# Centerboard_-_Prototype_2_WIP.net
KiCad netlist of a schematic drawn in EAGLE
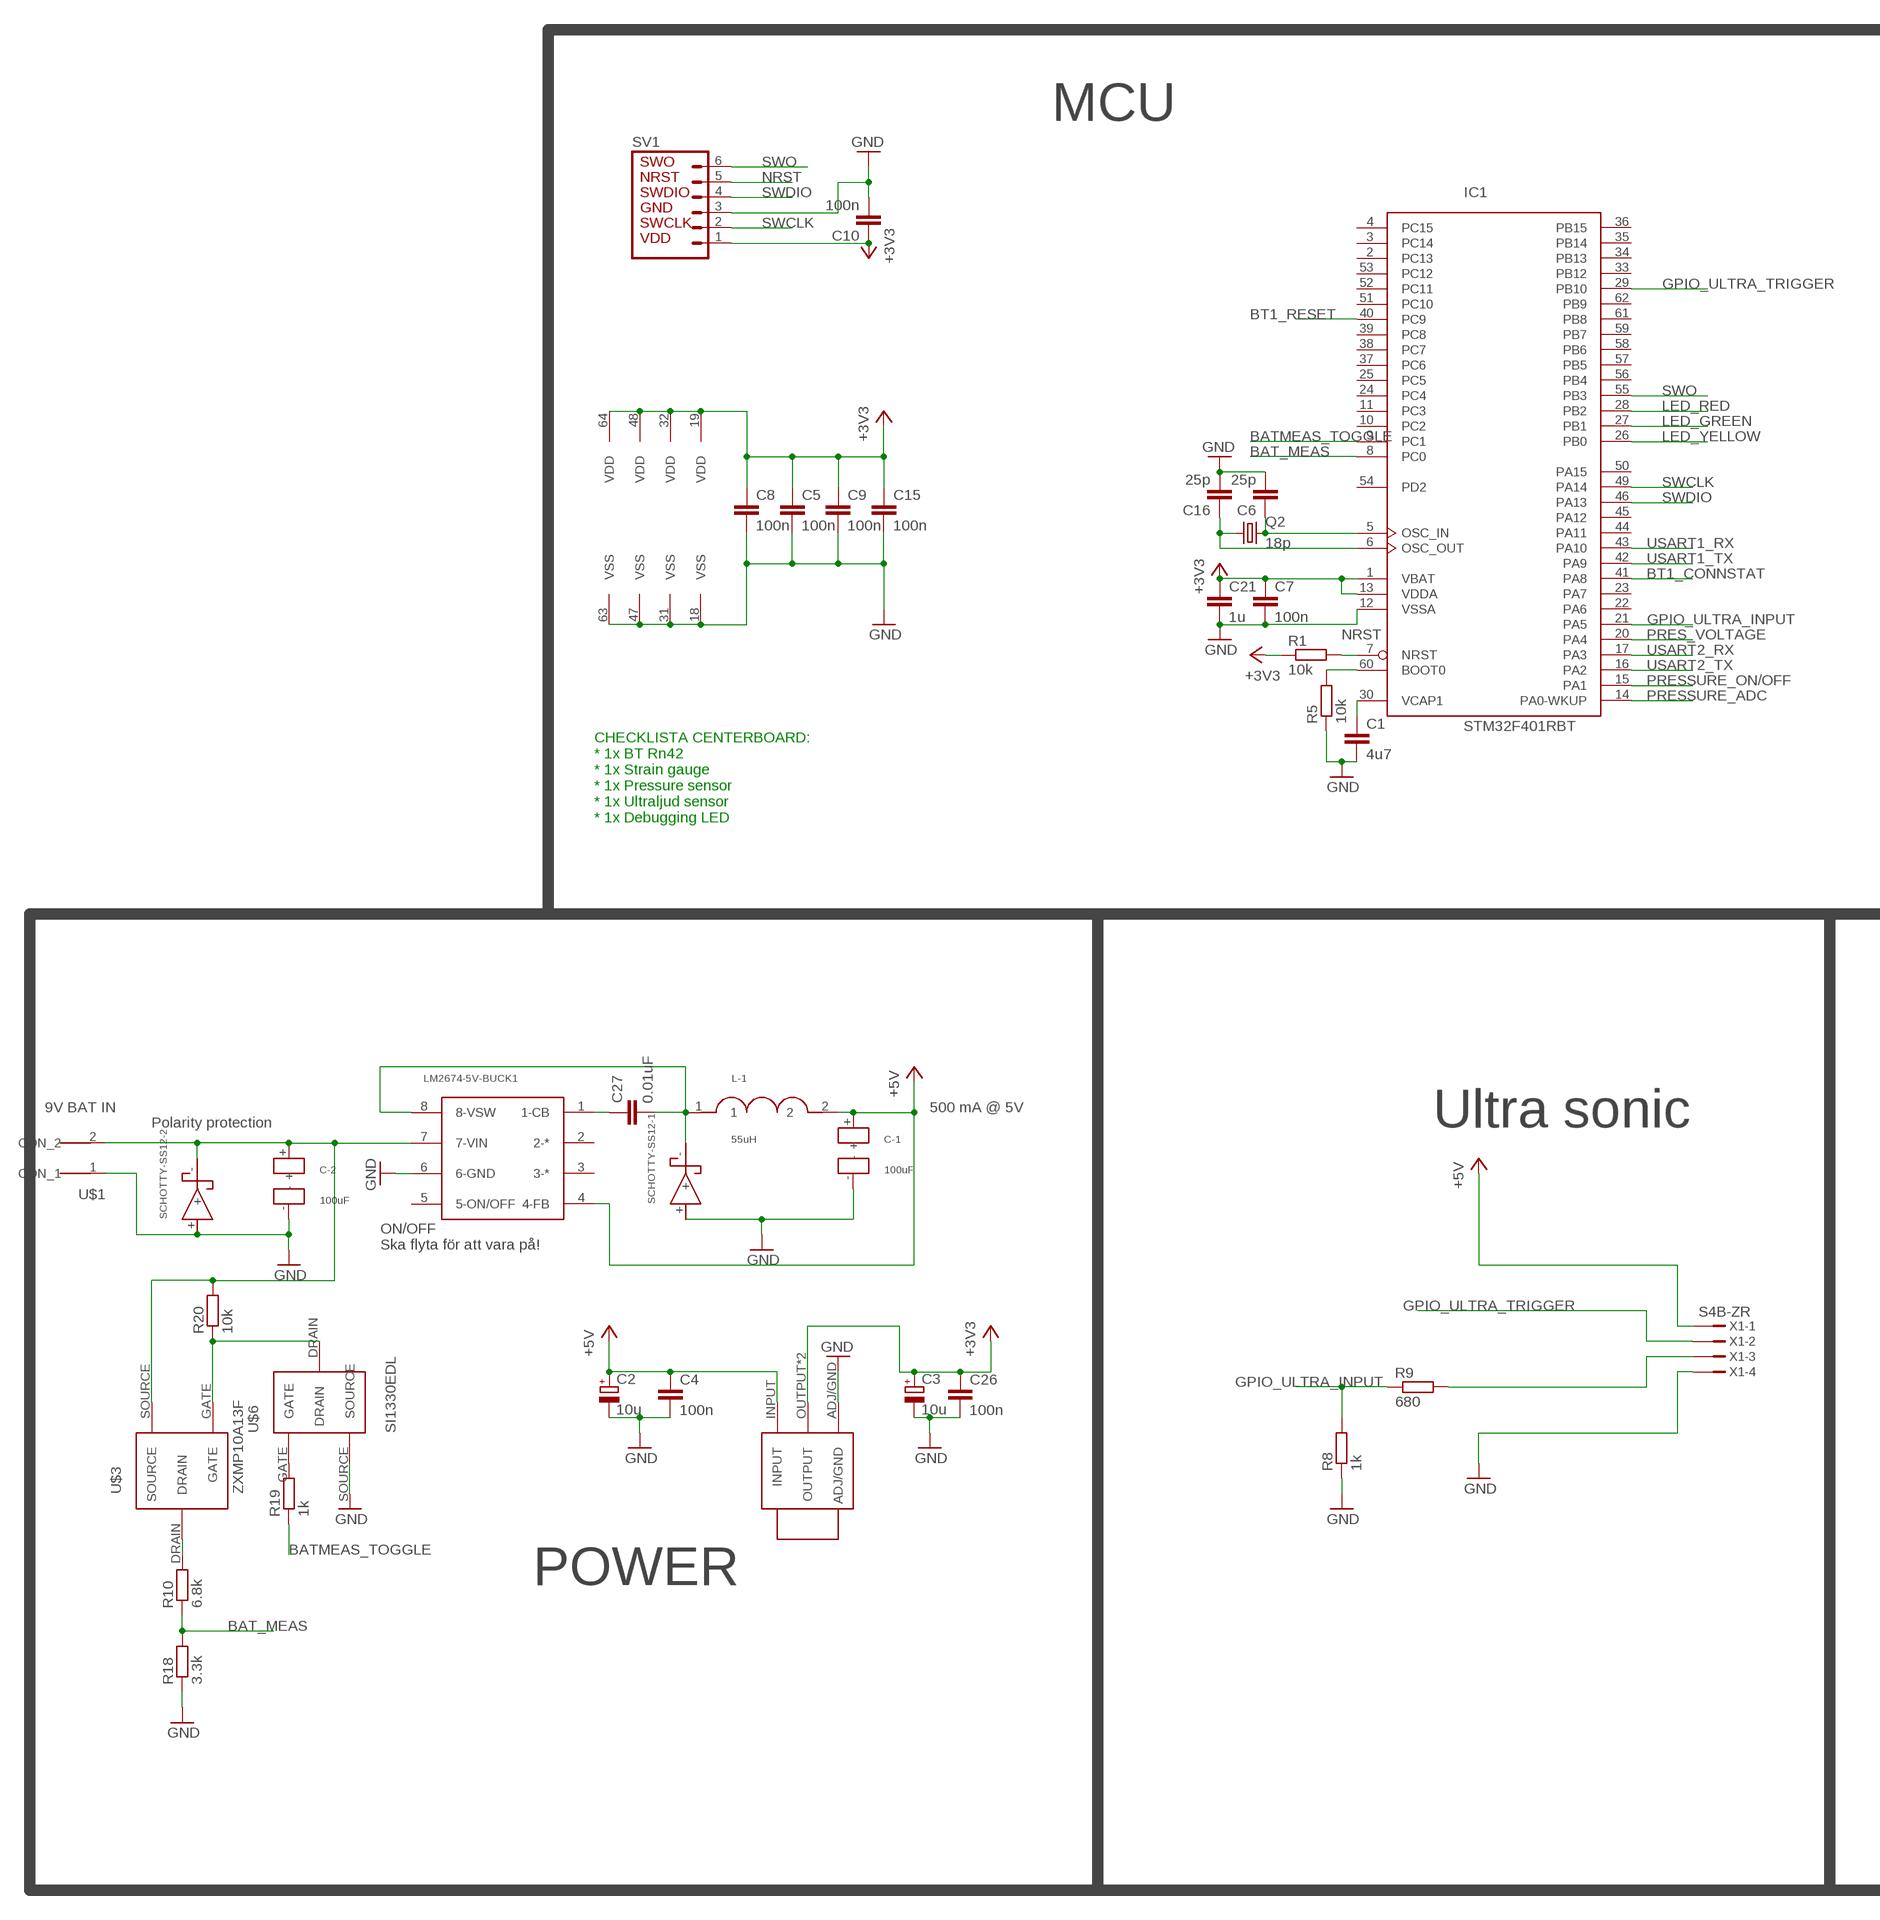
[diagram p0: schematic, sheet 1, part 1 of 2]
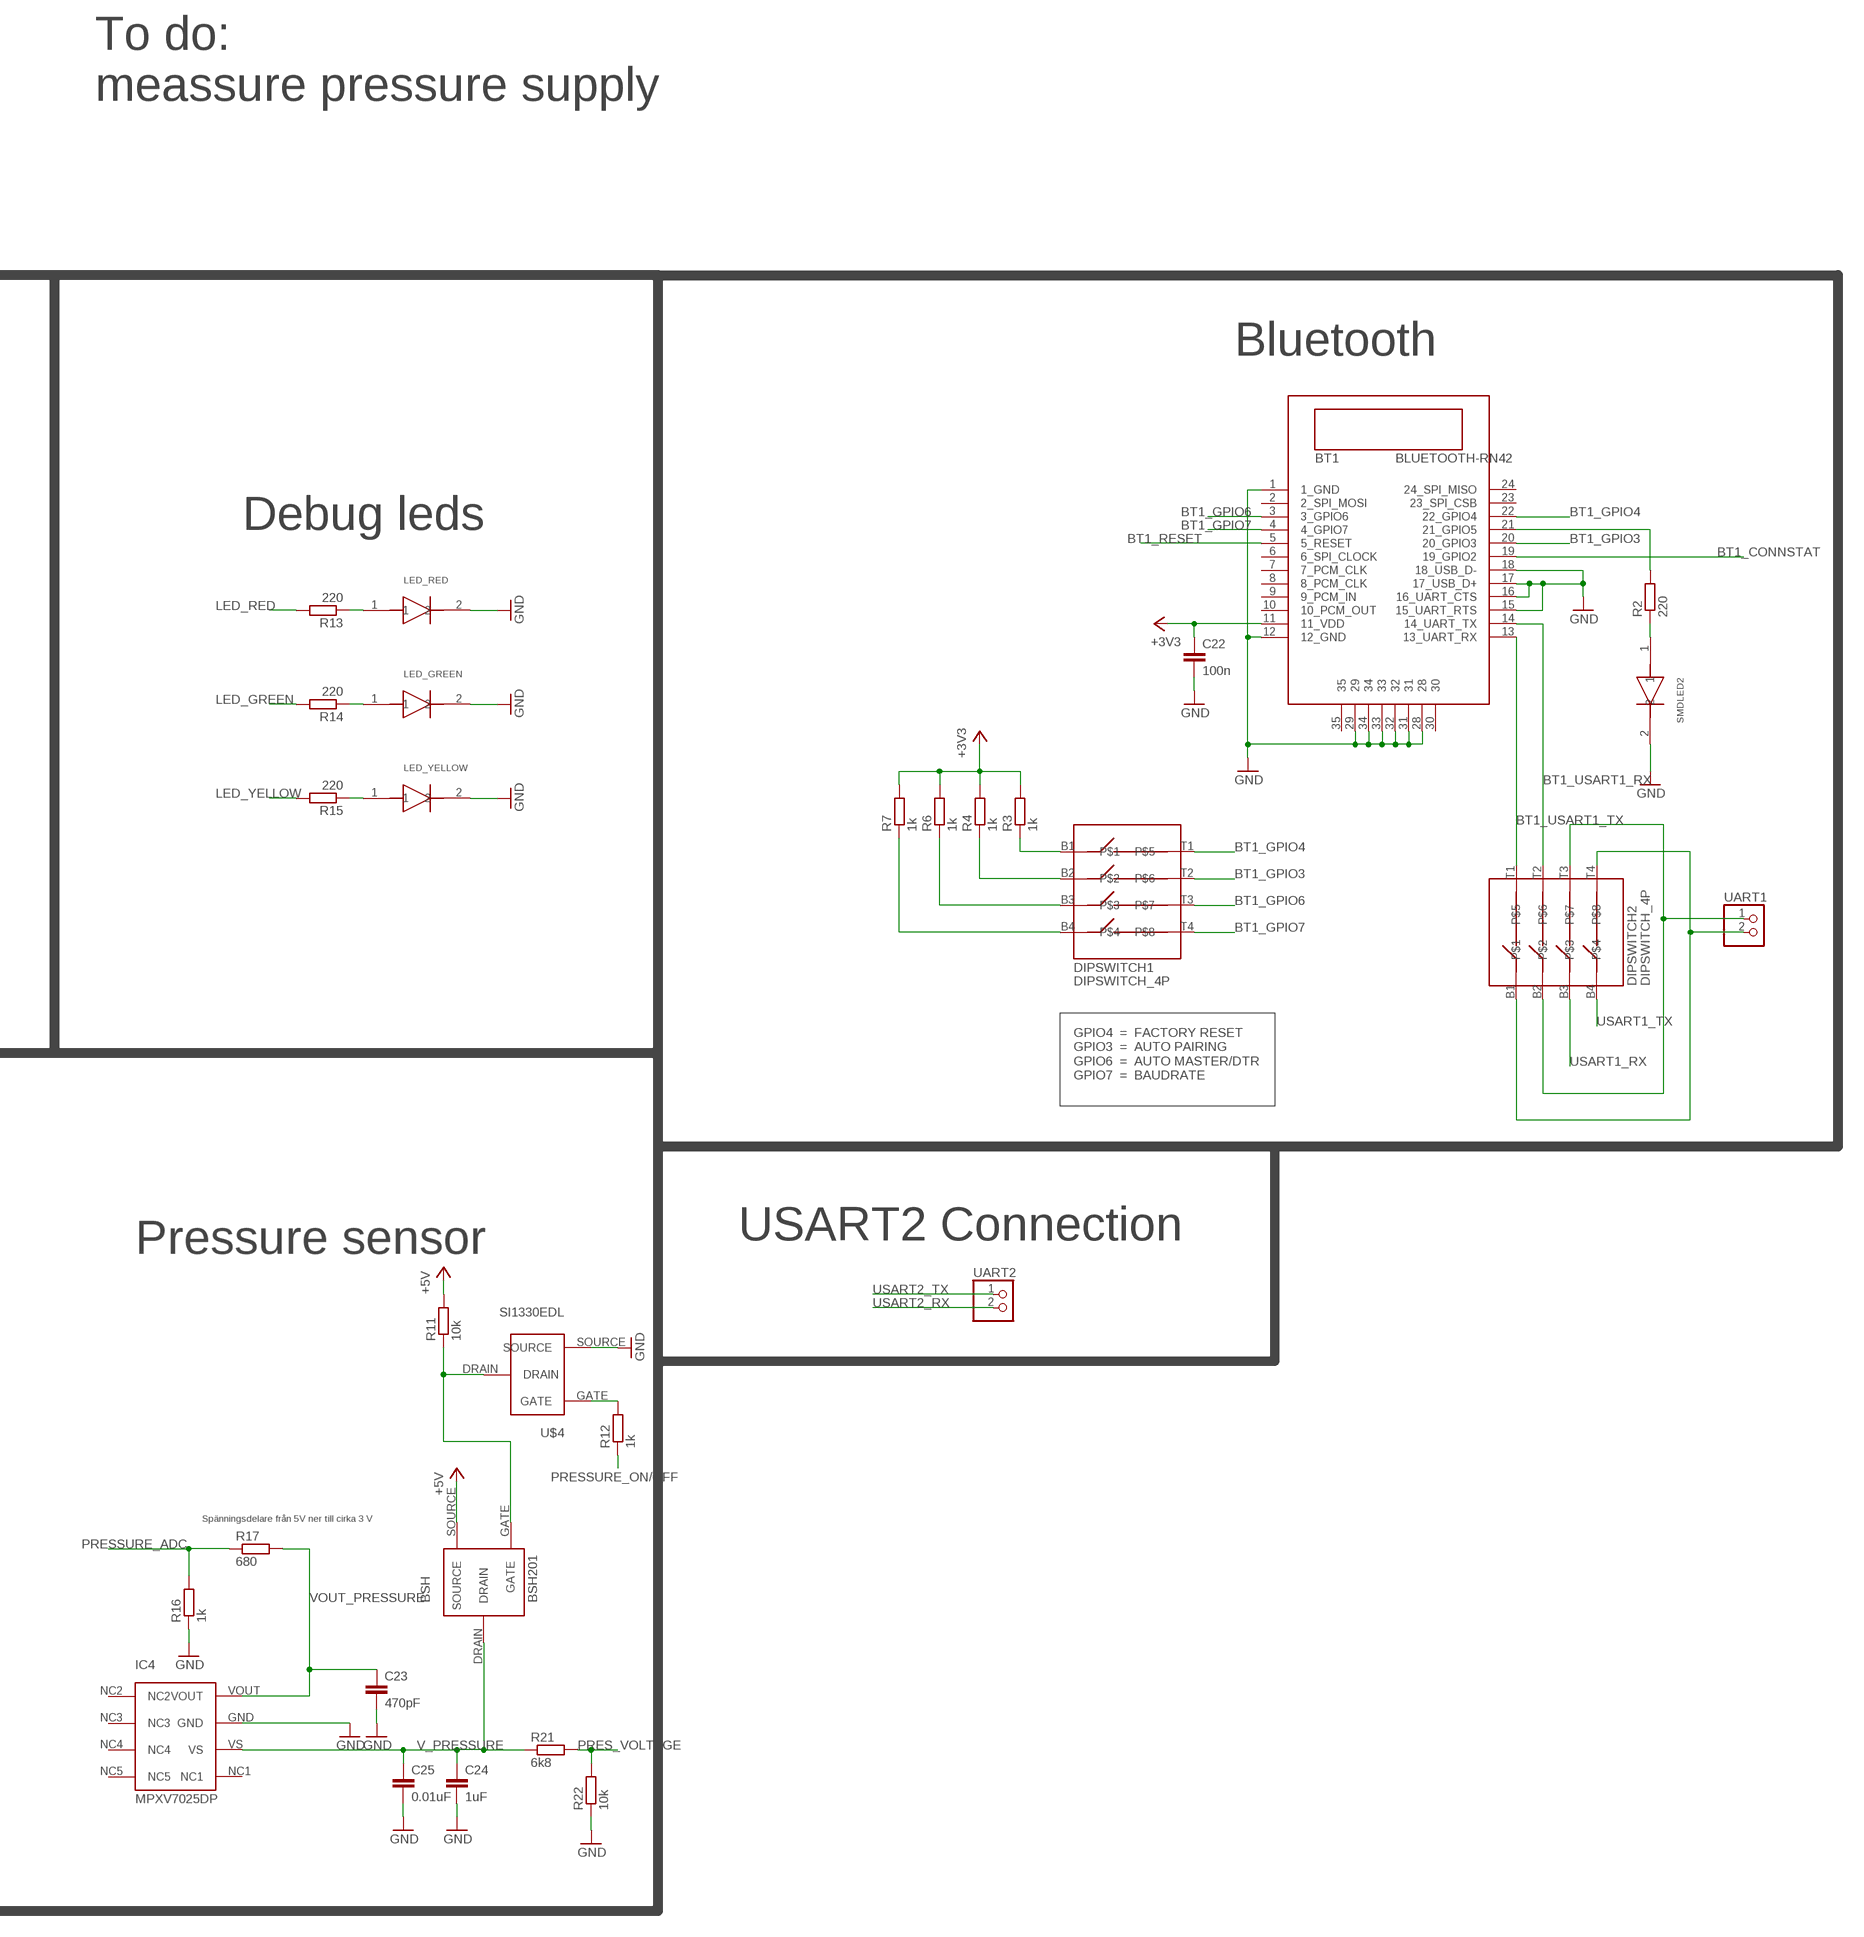
[diagram p1: schematic, sheet 1, part 2 of 2]

(export (version "E")
  (design (tool "Eeschema 10.0.6"))
  (components
    (comp (ref "BSH")
      (value "BSH201")
      (footprint "eagle-import:P-CHANNEL")
      (libsource (lib "eagle-import") (part "BSH201"))
    )
    (comp (ref "BT1")
      (value "BLUETOOTH-RN42")
      (footprint "eagle-import:RN42")
      (libsource (lib "eagle-import") (part "BLUETOOTH-RN42"))
    )
    (comp (ref "C-1")
      (value "100uF")
      (footprint "eagle-import:CAP-6.3MM-DIA")
      (libsource (lib "eagle-import") (part "PANASONIC-CAP"))
    )
    (comp (ref "C-2")
      (value "100uF")
      (footprint "eagle-import:CAP-6.3MM-DIA")
      (libsource (lib "eagle-import") (part "PANASONIC-CAP"))
    )
    (comp (ref "C1")
      (value "4u7")
      (footprint "eagle-import:C0805")
      (libsource (lib "eagle-import") (part "C-EUC0805"))
    )
    (comp (ref "C2")
      (value "10u")
      (footprint "eagle-import:153CLV-0505")
      (libsource (lib "eagle-import") (part "CPOL-EU153CLV-0505"))
    )
    (comp (ref "C3")
      (value "10u")
      (footprint "eagle-import:153CLV-0505")
      (libsource (lib "eagle-import") (part "CPOL-EU153CLV-0505"))
    )
    (comp (ref "C4")
      (value "100n")
      (footprint "eagle-import:C0805")
      (libsource (lib "eagle-import") (part "C-EUC0805"))
    )
    (comp (ref "C5")
      (value "100n")
      (footprint "eagle-import:C0805")
      (libsource (lib "eagle-import") (part "C-EUC0805"))
    )
    (comp (ref "C6")
      (value "25p")
      (footprint "eagle-import:C0805")
      (libsource (lib "eagle-import") (part "C-EUC0805"))
    )
    (comp (ref "C7")
      (value "100n")
      (footprint "eagle-import:C0805")
      (libsource (lib "eagle-import") (part "C-EUC0805"))
    )
    (comp (ref "C8")
      (value "100n")
      (footprint "eagle-import:C0805")
      (libsource (lib "eagle-import") (part "C-EUC0805"))
    )
    (comp (ref "C9")
      (value "100n")
      (footprint "eagle-import:C0805")
      (libsource (lib "eagle-import") (part "C-EUC0805"))
    )
    (comp (ref "C10")
      (value "100n")
      (footprint "eagle-import:C0805")
      (libsource (lib "eagle-import") (part "C-EUC0805"))
    )
    (comp (ref "C15")
      (value "100n")
      (footprint "eagle-import:C0805")
      (libsource (lib "eagle-import") (part "C-EUC0805"))
    )
    (comp (ref "C16")
      (value "25p")
      (footprint "eagle-import:C0805")
      (libsource (lib "eagle-import") (part "C-EUC0805"))
    )
    (comp (ref "C21")
      (value "1u")
      (footprint "eagle-import:C0805")
      (libsource (lib "eagle-import") (part "C-EUC0805"))
    )
    (comp (ref "C22")
      (value "100n")
      (footprint "eagle-import:C0805")
      (libsource (lib "eagle-import") (part "C-EUC0805"))
    )
    (comp (ref "C23")
      (value "470pF")
      (footprint "eagle-import:C0805")
      (libsource (lib "eagle-import") (part "C-EUC0805"))
    )
    (comp (ref "C24")
      (value "1uF")
      (footprint "eagle-import:C0805")
      (libsource (lib "eagle-import") (part "C-EUC0805"))
    )
    (comp (ref "C25")
      (value "0.01uF")
      (footprint "eagle-import:C0805")
      (libsource (lib "eagle-import") (part "C-EUC0805"))
    )
    (comp (ref "C26")
      (value "100n")
      (footprint "eagle-import:C0805")
      (libsource (lib "eagle-import") (part "C-EUC0805"))
    )
    (comp (ref "C27")
      (value "0.01uF")
      (footprint "eagle-import:C0805")
      (libsource (lib "eagle-import") (part "C-EUC0805"))
    )
    (comp (ref "DIPSWITCH1")
      (value "DIPSWITCH_4P")
      (footprint "eagle-import:DIPSWITCH4P")
      (libsource (lib "eagle-import") (part "DIPSWITCH_4P"))
    )
    (comp (ref "DIPSWITCH2")
      (value "DIPSWITCH_4P")
      (footprint "eagle-import:DIPSWITCH4P")
      (libsource (lib "eagle-import") (part "DIPSWITCH_4P"))
    )
    (comp (ref "IC1")
      (value "STM32F401RBT")
      (footprint "eagle-import:LQFP64")
      (libsource (lib "eagle-import") (part "STM32F401RTB"))
    )
    (comp (ref "IC4")
      (value "MPXV7025DP")
      (footprint "eagle-import:CASE1351-01")
      (libsource (lib "eagle-import") (part "MPXV7025DP"))
    )
    (comp (ref "L-1")
      (value "55uH")
      (footprint "eagle-import:INDUCTOR")
      (libsource (lib "eagle-import") (part "55UH-INDUKTOR"))
    )
    (comp (ref "LED_GREEN")
      (value "SMD_LED")
      (footprint "eagle-import:SMD_LED_CUSTOM")
      (libsource (lib "eagle-import") (part "SMD_LED"))
    )
    (comp (ref "LED_RED")
      (value "SMD_LED")
      (footprint "eagle-import:SMD_LED_CUSTOM")
      (libsource (lib "eagle-import") (part "SMD_LED"))
    )
    (comp (ref "LED_YELLOW")
      (value "SMD_LED")
      (footprint "eagle-import:SMD_LED_CUSTOM")
      (libsource (lib "eagle-import") (part "SMD_LED"))
    )
    (comp (ref "LM1117-1")
      (value "LM1117")
      (footprint "eagle-import:LM1117")
      (libsource (lib "eagle-import") (part "LM1117"))
    )
    (comp (ref "LM2674-5V-BUCK1")
      (value "LM2674-5VBUCK")
      (footprint "eagle-import:LM2674")
      (libsource (lib "eagle-import") (part "LM2674-5VBUCK"))
    )
    (comp (ref "Q2")
      (value "18p")
      (footprint "eagle-import:HC49UP")
      (libsource (lib "eagle-import") (part "CRYSTALHC49UP"))
    )
    (comp (ref "R1")
      (value "10k")
      (footprint "eagle-import:R0805")
      (libsource (lib "eagle-import") (part "R-EU_R0805"))
    )
    (comp (ref "R2")
      (value "220")
      (footprint "eagle-import:R0805")
      (libsource (lib "eagle-import") (part "resistor_R-EU_R0805"))
    )
    (comp (ref "R3")
      (value "1k")
      (footprint "eagle-import:R0805")
      (libsource (lib "eagle-import") (part "resistor_R-EU_R0805"))
    )
    (comp (ref "R4")
      (value "1k")
      (footprint "eagle-import:R0805")
      (libsource (lib "eagle-import") (part "resistor_R-EU_R0805"))
    )
    (comp (ref "R5")
      (value "10k")
      (footprint "eagle-import:R0805")
      (libsource (lib "eagle-import") (part "R-EU_R0805"))
    )
    (comp (ref "R6")
      (value "1k")
      (footprint "eagle-import:R0805")
      (libsource (lib "eagle-import") (part "resistor_R-EU_R0805"))
    )
    (comp (ref "R7")
      (value "1k")
      (footprint "eagle-import:R0805")
      (libsource (lib "eagle-import") (part "resistor_R-EU_R0805"))
    )
    (comp (ref "R8")
      (value "1k")
      (footprint "eagle-import:R0805")
      (libsource (lib "eagle-import") (part "R-EU_R0805"))
    )
    (comp (ref "R9")
      (value "680")
      (footprint "eagle-import:R0805")
      (libsource (lib "eagle-import") (part "R-EU_R0805"))
    )
    (comp (ref "R10")
      (value "6.8k")
      (footprint "eagle-import:R0805")
      (libsource (lib "eagle-import") (part "R-EU_R0805"))
    )
    (comp (ref "R11")
      (value "10k")
      (footprint "eagle-import:R0805")
      (libsource (lib "eagle-import") (part "R-EU_R0805"))
    )
    (comp (ref "R12")
      (value "1k")
      (footprint "eagle-import:R0805")
      (libsource (lib "eagle-import") (part "R-EU_R0805"))
    )
    (comp (ref "R13")
      (value "220")
      (footprint "eagle-import:R0805")
      (libsource (lib "eagle-import") (part "resistor_R-EU_R0805"))
    )
    (comp (ref "R14")
      (value "220")
      (footprint "eagle-import:R0805")
      (libsource (lib "eagle-import") (part "resistor_R-EU_R0805"))
    )
    (comp (ref "R15")
      (value "220")
      (footprint "eagle-import:R0805")
      (libsource (lib "eagle-import") (part "resistor_R-EU_R0805"))
    )
    (comp (ref "R16")
      (value "1k")
      (footprint "eagle-import:R0805")
      (libsource (lib "eagle-import") (part "R-EU_R0805"))
    )
    (comp (ref "R17")
      (value "680")
      (footprint "eagle-import:R0805")
      (libsource (lib "eagle-import") (part "R-EU_R0805"))
    )
    (comp (ref "R18")
      (value "3.3k")
      (footprint "eagle-import:R0805")
      (libsource (lib "eagle-import") (part "R-EU_R0805"))
    )
    (comp (ref "R19")
      (value "1k")
      (footprint "eagle-import:R0805")
      (libsource (lib "eagle-import") (part "R-EU_R0805"))
    )
    (comp (ref "R20")
      (value "10k")
      (footprint "eagle-import:R0805")
      (libsource (lib "eagle-import") (part "R-EU_R0805"))
    )
    (comp (ref "R21")
      (value "6k8")
      (footprint "eagle-import:R0805")
      (libsource (lib "eagle-import") (part "R-EU_R0805"))
    )
    (comp (ref "R22")
      (value "10k")
      (footprint "eagle-import:R0805")
      (libsource (lib "eagle-import") (part "R-EU_R0805"))
    )
    (comp (ref "SCHOTTY-SS12-1")
      (value "SCHOTTY-SS12")
      (footprint "eagle-import:SCHOTTY")
      (libsource (lib "eagle-import") (part "SCHOTTY-SS12"))
    )
    (comp (ref "SCHOTTY-SS12-2")
      (value "SCHOTTY-SS12")
      (footprint "eagle-import:SCHOTTY")
      (libsource (lib "eagle-import") (part "SCHOTTY-SS12"))
    )
    (comp (ref "SMDLED2")
      (value "SMD_LED")
      (footprint "eagle-import:SMD_LED_CUSTOM")
      (libsource (lib "eagle-import") (part "SMD_LED"))
    )
    (comp (ref "SV1")
      (value "MA06-1")
      (footprint "eagle-import:MA06-1")
      (libsource (lib "eagle-import") (part "MA06-1"))
    )
    (comp (ref "U$1")
      (value "JST-2WAYS")
      (footprint "eagle-import:JST-2WAYS")
      (libsource (lib "eagle-import") (part "JST-2WAYS"))
    )
    (comp (ref "U$3")
      (value "ZXMP10A13F")
      (footprint "eagle-import:P-CHANNEL")
      (libsource (lib "eagle-import") (part "ZXMP10A13F"))
    )
    (comp (ref "U$4")
      (value "SI1330EDL")
      (footprint "eagle-import:SOT-323")
      (libsource (lib "eagle-import") (part "SI1330EDL"))
    )
    (comp (ref "U$6")
      (value "SI1330EDL")
      (footprint "eagle-import:SOT-323")
      (libsource (lib "eagle-import") (part "SI1330EDL"))
    )
    (comp (ref "UART1")
      (value "PINHD-1X2")
      (footprint "eagle-import:1X02")
      (libsource (lib "eagle-import") (part "PINHD-1X2"))
    )
    (comp (ref "UART2")
      (value "PINHD-1X2")
      (footprint "eagle-import:1X02")
      (libsource (lib "eagle-import") (part "PINHD-1X2"))
    )
    (comp (ref "X1")
      (value "S4B-ZR")
      (footprint "eagle-import:S4B-ZR")
      (fields (field (name "MF") "FARNELL") (field (name "MPN") "S4B-ZR(LF)(SN)"))
      (libsource (lib "eagle-import") (part "?4B-ZRS"))
    )
  )
  (nets
    (net (code "1") (name "+3V3") (class "Default")
      (node (ref "BT1") (pin "11") (pinfunction "11_VDD_11") (pintype "bidirectional"))
      (node (ref "C10") (pin "1") (pinfunction "1_1") (pintype "passive"))
      (node (ref "C15") (pin "1") (pinfunction "1_1") (pintype "passive"))
      (node (ref "C21") (pin "1") (pinfunction "1_1") (pintype "passive"))
      (node (ref "C22") (pin "1") (pinfunction "1_1") (pintype "passive"))
      (node (ref "C26") (pin "1") (pinfunction "1_1") (pintype "passive"))
      (node (ref "C3") (pin "+") (pinfunction "+_+") (pintype "passive"))
      (node (ref "C5") (pin "1") (pinfunction "1_1") (pintype "passive"))
      (node (ref "C7") (pin "1") (pinfunction "1_1") (pintype "passive"))
      (node (ref "C8") (pin "1") (pinfunction "1_1") (pintype "passive"))
      (node (ref "C9") (pin "1") (pinfunction "1_1") (pintype "passive"))
      (node (ref "IC1") (pin "1") (pinfunction "VBAT_1") (pintype "power_in"))
      (node (ref "IC1") (pin "13") (pinfunction "VDDA_13") (pintype "power_in"))
      (node (ref "IC1") (pin "19") (pinfunction "VDD_19") (pintype "power_in"))
      (node (ref "IC1") (pin "32") (pinfunction "VDD_32") (pintype "power_in"))
      (node (ref "IC1") (pin "48") (pinfunction "VDD_48") (pintype "power_in"))
      (node (ref "IC1") (pin "64") (pinfunction "VDD_64") (pintype "power_in"))
      (node (ref "LM1117-1") (pin "OUTPUT") (pinfunction "OUTPUT_OUTPUT") (pintype "bidirectional"))
      (node (ref "LM1117-1") (pin "OUTPUT2") (pinfunction "OUTPUT_OUTPUT2") (pintype "bidirectional"))
      (node (ref "R1") (pin "1") (pinfunction "1_1") (pintype "passive"))
      (node (ref "R3") (pin "2") (pinfunction "2_2") (pintype "passive"))
      (node (ref "R4") (pin "2") (pinfunction "2_2") (pintype "passive"))
      (node (ref "R6") (pin "2") (pinfunction "2_2") (pintype "passive"))
      (node (ref "R7") (pin "2") (pinfunction "2_2") (pintype "passive"))
      (node (ref "SV1") (pin "1") (pinfunction "1_1") (pintype "passive"))
    )
    (net (code "2") (name "+5V") (class "Default")
      (node (ref "BSH") (pin "SOURCE") (pinfunction "SOURCE_SOURCE") (pintype "bidirectional"))
      (node (ref "C-1") (pin "+") (pinfunction "+_+") (pintype "bidirectional"))
      (node (ref "C2") (pin "+") (pinfunction "+_+") (pintype "passive"))
      (node (ref "C4") (pin "1") (pinfunction "1_1") (pintype "passive"))
      (node (ref "L-1") (pin "2") (pinfunction "2_2") (pintype "bidirectional"))
      (node (ref "LM1117-1") (pin "INPUT") (pinfunction "INPUT_INPUT") (pintype "bidirectional"))
      (node (ref "LM2674-5V-BUCK1") (pin "4") (pinfunction "4-FB_4") (pintype "bidirectional"))
      (node (ref "R11") (pin "2") (pinfunction "2_2") (pintype "passive"))
      (node (ref "X1") (pin "1") (pinfunction "1_1") (pintype "passive"))
    )
    (net (code "3") (name "/BATMEAS_TOGGLE") (class "Default")
      (node (ref "IC1") (pin "9") (pinfunction "PC1_9") (pintype "bidirectional"))
      (node (ref "R19") (pin "1") (pinfunction "1_1") (pintype "passive"))
    )
    (net (code "4") (name "/BAT_MEAS") (class "Default")
      (node (ref "IC1") (pin "8") (pinfunction "PC0_8") (pintype "bidirectional"))
      (node (ref "R10") (pin "1") (pinfunction "1_1") (pintype "passive"))
      (node (ref "R18") (pin "2") (pinfunction "2_2") (pintype "passive"))
    )
    (net (code "5") (name "/BT1_CONNSTAT") (class "Default")
      (node (ref "BT1") (pin "19") (pinfunction "19_GPIO2_19") (pintype "bidirectional"))
      (node (ref "IC1") (pin "41") (pinfunction "PA8_41") (pintype "bidirectional"))
    )
    (net (code "6") (name "/BT1_GPIO3") (class "Default")
      (node (ref "BT1") (pin "20") (pinfunction "20_GPIO3_20") (pintype "bidirectional"))
      (node (ref "DIPSWITCH1") (pin "T2") (pinfunction "P$6_T2") (pintype "bidirectional"))
    )
    (net (code "7") (name "/BT1_GPIO4") (class "Default")
      (node (ref "BT1") (pin "22") (pinfunction "22_GPIO4_22") (pintype "bidirectional"))
      (node (ref "DIPSWITCH1") (pin "T1") (pinfunction "P$5_T1") (pintype "bidirectional"))
    )
    (net (code "8") (name "/BT1_GPIO6") (class "Default")
      (node (ref "BT1") (pin "3") (pinfunction "3_GPIO6_3") (pintype "bidirectional"))
      (node (ref "DIPSWITCH1") (pin "T3") (pinfunction "P$7_T3") (pintype "bidirectional"))
    )
    (net (code "9") (name "/BT1_GPIO7") (class "Default")
      (node (ref "BT1") (pin "4") (pinfunction "4_GPIO7_4") (pintype "bidirectional"))
      (node (ref "DIPSWITCH1") (pin "T4") (pinfunction "P$8_T4") (pintype "bidirectional"))
    )
    (net (code "10") (name "/BT1_RESET") (class "Default")
      (node (ref "BT1") (pin "5") (pinfunction "5_RESET_5") (pintype "bidirectional"))
      (node (ref "IC1") (pin "40") (pinfunction "PC9_40") (pintype "bidirectional"))
    )
    (net (code "11") (name "/BT1_USART1_RX") (class "Default")
      (node (ref "BT1") (pin "14") (pinfunction "14_UART_TX_14") (pintype "bidirectional"))
      (node (ref "DIPSWITCH2") (pin "T2") (pinfunction "P$6_T2") (pintype "bidirectional"))
    )
    (net (code "12") (name "/BT1_USART1_TX") (class "Default")
      (node (ref "BT1") (pin "13") (pinfunction "13_UART_RX_13") (pintype "bidirectional"))
      (node (ref "DIPSWITCH2") (pin "T1") (pinfunction "P$5_T1") (pintype "bidirectional"))
    )
    (net (code "13") (name "/GPIO_ULTRA_INPUT") (class "Default")
      (node (ref "IC1") (pin "21") (pinfunction "PA5_21") (pintype "bidirectional"))
      (node (ref "R8") (pin "2") (pinfunction "2_2") (pintype "passive"))
      (node (ref "R9") (pin "1") (pinfunction "1_1") (pintype "passive"))
    )
    (net (code "14") (name "/GPIO_ULTRA_TRIGGER") (class "Default")
      (node (ref "IC1") (pin "29") (pinfunction "PB10_29") (pintype "bidirectional"))
      (node (ref "X1") (pin "2") (pinfunction "1_2") (pintype "passive"))
    )
    (net (code "15") (name "/LED_GREEN") (class "Default")
      (node (ref "IC1") (pin "27") (pinfunction "PB1_27") (pintype "bidirectional"))
      (node (ref "R14") (pin "2") (pinfunction "2_2") (pintype "passive"))
    )
    (net (code "16") (name "/LED_RED") (class "Default")
      (node (ref "IC1") (pin "28") (pinfunction "PB2_28") (pintype "bidirectional"))
      (node (ref "R13") (pin "2") (pinfunction "2_2") (pintype "passive"))
    )
    (net (code "17") (name "/LED_YELLOW") (class "Default")
      (node (ref "IC1") (pin "26") (pinfunction "PB0_26") (pintype "bidirectional"))
      (node (ref "R15") (pin "2") (pinfunction "2_2") (pintype "passive"))
    )
    (net (code "18") (name "/NRST") (class "Default")
      (node (ref "IC1") (pin "7") (pinfunction "NRST_7") (pintype "bidirectional"))
      (node (ref "R1") (pin "2") (pinfunction "2_2") (pintype "passive"))
      (node (ref "SV1") (pin "5") (pinfunction "5_5") (pintype "passive"))
    )
    (net (code "19") (name "/PRESSURE_ADC") (class "Default")
      (node (ref "IC1") (pin "14") (pinfunction "PA0-WKUP_14") (pintype "bidirectional"))
      (node (ref "R16") (pin "2") (pinfunction "2_2") (pintype "passive"))
      (node (ref "R17") (pin "1") (pinfunction "1_1") (pintype "passive"))
    )
    (net (code "20") (name "/PRESSURE_ON{slash}OFF") (class "Default")
      (node (ref "IC1") (pin "15") (pinfunction "PA1_15") (pintype "bidirectional"))
      (node (ref "R12") (pin "1") (pinfunction "1_1") (pintype "passive"))
    )
    (net (code "21") (name "/PRES_VOLTAGE") (class "Default")
      (node (ref "IC1") (pin "20") (pinfunction "PA4_20") (pintype "bidirectional"))
      (node (ref "R21") (pin "2") (pinfunction "2_2") (pintype "passive"))
      (node (ref "R22") (pin "2") (pinfunction "2_2") (pintype "passive"))
    )
    (net (code "22") (name "/SWCLK") (class "Default")
      (node (ref "IC1") (pin "49") (pinfunction "PA14_49") (pintype "bidirectional"))
      (node (ref "SV1") (pin "2") (pinfunction "2_2") (pintype "passive"))
    )
    (net (code "23") (name "/SWDIO") (class "Default")
      (node (ref "IC1") (pin "46") (pinfunction "PA13_46") (pintype "bidirectional"))
      (node (ref "SV1") (pin "4") (pinfunction "4_4") (pintype "passive"))
    )
    (net (code "24") (name "/SWO") (class "Default")
      (node (ref "IC1") (pin "55") (pinfunction "PB3_55") (pintype "bidirectional"))
      (node (ref "SV1") (pin "6") (pinfunction "6_6") (pintype "passive"))
    )
    (net (code "25") (name "/USART1_RX") (class "Default")
      (node (ref "DIPSWITCH2") (pin "B3") (pinfunction "P$3_B3") (pintype "bidirectional"))
      (node (ref "IC1") (pin "43") (pinfunction "PA10_43") (pintype "bidirectional"))
    )
    (net (code "26") (name "/USART1_TX") (class "Default")
      (node (ref "DIPSWITCH2") (pin "B4") (pinfunction "P$4_B4") (pintype "bidirectional"))
      (node (ref "IC1") (pin "42") (pinfunction "PA9_42") (pintype "bidirectional"))
    )
    (net (code "27") (name "/USART2_RX") (class "Default")
      (node (ref "IC1") (pin "17") (pinfunction "PA3_17") (pintype "bidirectional"))
      (node (ref "UART2") (pin "2") (pinfunction "2_2") (pintype "passive"))
    )
    (net (code "28") (name "/USART2_TX") (class "Default")
      (node (ref "IC1") (pin "16") (pinfunction "PA2_16") (pintype "bidirectional"))
      (node (ref "UART2") (pin "1") (pinfunction "1_1") (pintype "passive"))
    )
    (net (code "29") (name "/VOUT_PRESSURE") (class "Default")
      (node (ref "C23") (pin "1") (pinfunction "1_1") (pintype "passive"))
      (node (ref "IC4") (pin "VOUT") (pinfunction "VOUT_VOUT") (pintype "bidirectional"))
      (node (ref "R17") (pin "2") (pinfunction "2_2") (pintype "passive"))
    )
    (net (code "30") (name "/V_PRESSURE") (class "Default")
      (node (ref "BSH") (pin "DRAIN") (pinfunction "DRAIN_DRAIN") (pintype "bidirectional"))
      (node (ref "C24") (pin "1") (pinfunction "1_1") (pintype "passive"))
      (node (ref "C25") (pin "1") (pinfunction "1_1") (pintype "passive"))
      (node (ref "IC4") (pin "VS") (pinfunction "VS_VS") (pintype "bidirectional"))
      (node (ref "R21") (pin "1") (pinfunction "1_1") (pintype "passive"))
    )
    (net (code "31") (name "GND") (class "Default")
      (node (ref "BT1") (pin "1") (pinfunction "1_GND_1") (pintype "bidirectional"))
      (node (ref "BT1") (pin "12") (pinfunction "12_GND_12") (pintype "bidirectional"))
      (node (ref "BT1") (pin "15") (pinfunction "15_UART_RTS_15") (pintype "bidirectional"))
      (node (ref "BT1") (pin "16") (pinfunction "16_UART_CTS_16") (pintype "bidirectional"))
      (node (ref "BT1") (pin "17") (pinfunction "17_USB_D+_17") (pintype "bidirectional"))
      (node (ref "BT1") (pin "18") (pinfunction "18_USB_D-_18") (pintype "bidirectional"))
      (node (ref "BT1") (pin "28") (pinfunction "28_28") (pintype "bidirectional"))
      (node (ref "BT1") (pin "29") (pinfunction "29_29") (pintype "bidirectional"))
      (node (ref "BT1") (pin "31") (pinfunction "31_31") (pintype "bidirectional"))
      (node (ref "BT1") (pin "32") (pinfunction "32_32") (pintype "bidirectional"))
      (node (ref "BT1") (pin "33") (pinfunction "33_33") (pintype "bidirectional"))
      (node (ref "BT1") (pin "34") (pinfunction "34_34") (pintype "bidirectional"))
      (node (ref "C-1") (pin "-") (pinfunction "-_-") (pintype "bidirectional"))
      (node (ref "C-2") (pin "-") (pinfunction "-_-") (pintype "bidirectional"))
      (node (ref "C1") (pin "2") (pinfunction "2_2") (pintype "passive"))
      (node (ref "C10") (pin "2") (pinfunction "2_2") (pintype "passive"))
      (node (ref "C15") (pin "2") (pinfunction "2_2") (pintype "passive"))
      (node (ref "C16") (pin "2") (pinfunction "2_2") (pintype "passive"))
      (node (ref "C2") (pin "-") (pinfunction "-_-") (pintype "passive"))
      (node (ref "C21") (pin "2") (pinfunction "2_2") (pintype "passive"))
      (node (ref "C22") (pin "2") (pinfunction "2_2") (pintype "passive"))
      (node (ref "C23") (pin "2") (pinfunction "2_2") (pintype "passive"))
      (node (ref "C24") (pin "2") (pinfunction "2_2") (pintype "passive"))
      (node (ref "C25") (pin "2") (pinfunction "2_2") (pintype "passive"))
      (node (ref "C26") (pin "2") (pinfunction "2_2") (pintype "passive"))
      (node (ref "C3") (pin "-") (pinfunction "-_-") (pintype "passive"))
      (node (ref "C4") (pin "2") (pinfunction "2_2") (pintype "passive"))
      (node (ref "C5") (pin "2") (pinfunction "2_2") (pintype "passive"))
      (node (ref "C6") (pin "2") (pinfunction "2_2") (pintype "passive"))
      (node (ref "C7") (pin "2") (pinfunction "2_2") (pintype "passive"))
      (node (ref "C8") (pin "2") (pinfunction "2_2") (pintype "passive"))
      (node (ref "C9") (pin "2") (pinfunction "2_2") (pintype "passive"))
      (node (ref "IC1") (pin "12") (pinfunction "VSSA_12") (pintype "power_in"))
      (node (ref "IC1") (pin "18") (pinfunction "VSS_18") (pintype "power_in"))
      (node (ref "IC1") (pin "31") (pinfunction "VSS_31") (pintype "power_in"))
      (node (ref "IC1") (pin "47") (pinfunction "VSS_47") (pintype "power_in"))
      (node (ref "IC1") (pin "63") (pinfunction "VSS_63") (pintype "power_in"))
      (node (ref "IC4") (pin "GND") (pinfunction "GND_GND") (pintype "bidirectional"))
      (node (ref "LED_GREEN") (pin "2") (pinfunction "2_2") (pintype "bidirectional"))
      (node (ref "LED_RED") (pin "2") (pinfunction "2_2") (pintype "bidirectional"))
      (node (ref "LED_YELLOW") (pin "2") (pinfunction "2_2") (pintype "bidirectional"))
      (node (ref "LM1117-1") (pin "ADJ/GND") (pinfunction "ADJ/GND_ADJ/GND") (pintype "bidirectional"))
      (node (ref "LM2674-5V-BUCK1") (pin "6") (pinfunction "6-GND_6") (pintype "bidirectional"))
      (node (ref "R16") (pin "1") (pinfunction "1_1") (pintype "passive"))
      (node (ref "R18") (pin "1") (pinfunction "1_1") (pintype "passive"))
      (node (ref "R22") (pin "1") (pinfunction "1_1") (pintype "passive"))
      (node (ref "R5") (pin "1") (pinfunction "1_1") (pintype "passive"))
      (node (ref "R8") (pin "1") (pinfunction "1_1") (pintype "passive"))
      (node (ref "SCHOTTY-SS12-1") (pin "+") (pinfunction "+_+") (pintype "bidirectional"))
      (node (ref "SCHOTTY-SS12-2") (pin "+") (pinfunction "+_+") (pintype "bidirectional"))
      (node (ref "SMDLED2") (pin "2") (pinfunction "2_2") (pintype "bidirectional"))
      (node (ref "SV1") (pin "3") (pinfunction "3_3") (pintype "passive"))
      (node (ref "U$1") (pin "1") (pinfunction "CON_1_1") (pintype "bidirectional"))
      (node (ref "U$4") (pin "SOURCE") (pinfunction "SOURCE_SOURCE") (pintype "bidirectional"))
      (node (ref "U$6") (pin "SOURCE") (pinfunction "SOURCE_SOURCE") (pintype "bidirectional"))
      (node (ref "X1") (pin "4") (pinfunction "1_4") (pintype "passive"))
    )
    (net (code "32") (name "Net-(BSH-PadGATE)") (class "Default")
      (node (ref "BSH") (pin "GATE") (pinfunction "GATE_GATE") (pintype "bidirectional"))
      (node (ref "R11") (pin "1") (pinfunction "1_1") (pintype "passive"))
      (node (ref "U$4") (pin "DRAIN") (pinfunction "DRAIN_DRAIN") (pintype "bidirectional"))
    )
    (net (code "33") (name "Net-(BT1-21_GPIO5)") (class "Default")
      (node (ref "BT1") (pin "21") (pinfunction "21_GPIO5_21") (pintype "bidirectional"))
      (node (ref "R2") (pin "2") (pinfunction "2_2") (pintype "passive"))
    )
    (net (code "34") (name "Net-(DIPSWITCH1-P$1)") (class "Default")
      (node (ref "DIPSWITCH1") (pin "B1") (pinfunction "P$1_B1") (pintype "bidirectional"))
      (node (ref "R3") (pin "1") (pinfunction "1_1") (pintype "passive"))
    )
    (net (code "35") (name "Net-(DIPSWITCH1-P$2)") (class "Default")
      (node (ref "DIPSWITCH1") (pin "B2") (pinfunction "P$2_B2") (pintype "bidirectional"))
      (node (ref "R4") (pin "1") (pinfunction "1_1") (pintype "passive"))
    )
    (net (code "36") (name "Net-(DIPSWITCH1-P$3)") (class "Default")
      (node (ref "DIPSWITCH1") (pin "B3") (pinfunction "P$3_B3") (pintype "bidirectional"))
      (node (ref "R6") (pin "1") (pinfunction "1_1") (pintype "passive"))
    )
    (net (code "37") (name "Net-(DIPSWITCH1-P$4)") (class "Default")
      (node (ref "DIPSWITCH1") (pin "B4") (pinfunction "P$4_B4") (pintype "bidirectional"))
      (node (ref "R7") (pin "1") (pinfunction "1_1") (pintype "passive"))
    )
    (net (code "38") (name "Net-(DIPSWITCH2-P$1)") (class "Default")
      (node (ref "DIPSWITCH2") (pin "B1") (pinfunction "P$1_B1") (pintype "bidirectional"))
      (node (ref "DIPSWITCH2") (pin "T4") (pinfunction "P$8_T4") (pintype "bidirectional"))
      (node (ref "UART1") (pin "2") (pinfunction "2_2") (pintype "passive"))
    )
    (net (code "39") (name "Net-(DIPSWITCH2-P$2)") (class "Default")
      (node (ref "DIPSWITCH2") (pin "B2") (pinfunction "P$2_B2") (pintype "bidirectional"))
      (node (ref "DIPSWITCH2") (pin "T3") (pinfunction "P$7_T3") (pintype "bidirectional"))
      (node (ref "UART1") (pin "1") (pinfunction "1_1") (pintype "passive"))
    )
    (net (code "40") (name "Net-(IC1A-BOOT0)") (class "Default")
      (node (ref "IC1") (pin "60") (pinfunction "BOOT0_60") (pintype "input"))
      (node (ref "R5") (pin "2") (pinfunction "2_2") (pintype "passive"))
    )
    (net (code "41") (name "Net-(IC1A-OSC_IN)") (class "Default")
      (node (ref "C6") (pin "1") (pinfunction "1_1") (pintype "passive"))
      (node (ref "IC1") (pin "5") (pinfunction "OSC_IN_5") (pintype "bidirectional"))
      (node (ref "Q2") (pin "2") (pinfunction "2_2") (pintype "passive"))
    )
    (net (code "42") (name "Net-(IC1A-OSC_OUT)") (class "Default")
      (node (ref "C16") (pin "1") (pinfunction "1_1") (pintype "passive"))
      (node (ref "IC1") (pin "6") (pinfunction "OSC_OUT_6") (pintype "bidirectional"))
      (node (ref "Q2") (pin "1") (pinfunction "1_1") (pintype "passive"))
    )
    (net (code "43") (name "Net-(IC1A-VCAP1)") (class "Default")
      (node (ref "C1") (pin "1") (pinfunction "1_1") (pintype "passive"))
      (node (ref "IC1") (pin "30") (pinfunction "VCAP1_30") (pintype "power_in"))
    )
    (net (code "44") (name "Net-(LED_GREEN-Pad1)") (class "Default")
      (node (ref "LED_GREEN") (pin "1") (pinfunction "1_1") (pintype "bidirectional"))
      (node (ref "R14") (pin "1") (pinfunction "1_1") (pintype "passive"))
    )
    (net (code "45") (name "Net-(LED_RED-Pad1)") (class "Default")
      (node (ref "LED_RED") (pin "1") (pinfunction "1_1") (pintype "bidirectional"))
      (node (ref "R13") (pin "1") (pinfunction "1_1") (pintype "passive"))
    )
    (net (code "46") (name "Net-(LED_YELLOW-Pad1)") (class "Default")
      (node (ref "LED_YELLOW") (pin "1") (pinfunction "1_1") (pintype "bidirectional"))
      (node (ref "R15") (pin "1") (pinfunction "1_1") (pintype "passive"))
    )
    (net (code "47") (name "Net-(LM2674-5V-BUCK1-1-CB)") (class "Default")
      (node (ref "C27") (pin "1") (pinfunction "1_1") (pintype "passive"))
      (node (ref "LM2674-5V-BUCK1") (pin "1") (pinfunction "1-CB_1") (pintype "bidirectional"))
    )
    (net (code "48") (name "Net-(LM2674-5V-BUCK1-7-VIN)") (class "Default")
      (node (ref "C-2") (pin "+") (pinfunction "+_+") (pintype "bidirectional"))
      (node (ref "LM2674-5V-BUCK1") (pin "7") (pinfunction "7-VIN_7") (pintype "bidirectional"))
      (node (ref "R20") (pin "2") (pinfunction "2_2") (pintype "passive"))
      (node (ref "SCHOTTY-SS12-2") (pin "-") (pinfunction "-_-") (pintype "bidirectional"))
      (node (ref "U$1") (pin "2") (pinfunction "CON_2_2") (pintype "bidirectional"))
      (node (ref "U$3") (pin "SOURCE") (pinfunction "SOURCE_SOURCE") (pintype "bidirectional"))
    )
    (net (code "49") (name "Net-(LM2674-5V-BUCK1-8-VSW)") (class "Default")
      (node (ref "C27") (pin "2") (pinfunction "2_2") (pintype "passive"))
      (node (ref "L-1") (pin "1") (pinfunction "1_1") (pintype "bidirectional"))
      (node (ref "LM2674-5V-BUCK1") (pin "8") (pinfunction "8-VSW_8") (pintype "bidirectional"))
      (node (ref "SCHOTTY-SS12-1") (pin "-") (pinfunction "-_-") (pintype "bidirectional"))
    )
    (net (code "50") (name "Net-(R2-Pad1)") (class "Default")
      (node (ref "R2") (pin "1") (pinfunction "1_1") (pintype "passive"))
      (node (ref "SMDLED2") (pin "1") (pinfunction "1_1") (pintype "bidirectional"))
    )
    (net (code "51") (name "Net-(R10-Pad2)") (class "Default")
      (node (ref "R10") (pin "2") (pinfunction "2_2") (pintype "passive"))
      (node (ref "U$3") (pin "DRAIN") (pinfunction "DRAIN_DRAIN") (pintype "bidirectional"))
    )
    (net (code "52") (name "Net-(R12-Pad2)") (class "Default")
      (node (ref "R12") (pin "2") (pinfunction "2_2") (pintype "passive"))
      (node (ref "U$4") (pin "GATE") (pinfunction "GATE_GATE") (pintype "bidirectional"))
    )
    (net (code "53") (name "Net-(R19-Pad2)") (class "Default")
      (node (ref "R19") (pin "2") (pinfunction "2_2") (pintype "passive"))
      (node (ref "U$6") (pin "GATE") (pinfunction "GATE_GATE") (pintype "bidirectional"))
    )
    (net (code "54") (name "Net-(R20-Pad1)") (class "Default")
      (node (ref "R20") (pin "1") (pinfunction "1_1") (pintype "passive"))
      (node (ref "U$3") (pin "GATE") (pinfunction "GATE_GATE") (pintype "bidirectional"))
      (node (ref "U$6") (pin "DRAIN") (pinfunction "DRAIN_DRAIN") (pintype "bidirectional"))
    )
    (net (code "55") (name "Net-(X1C-1)") (class "Default")
      (node (ref "R9") (pin "2") (pinfunction "2_2") (pintype "passive"))
      (node (ref "X1") (pin "3") (pinfunction "1_3") (pintype "passive"))
    )
    (net (code "56") (name "unconnected-(BT1-2_SPI_MOSI-Pad2)") (class "Default")
      (node (ref "BT1") (pin "2") (pinfunction "2_SPI_MOSI_2") (pintype "bidirectional"))
    )
    (net (code "57") (name "unconnected-(BT1-6_SPI_CLOCK-Pad6)") (class "Default")
      (node (ref "BT1") (pin "6") (pinfunction "6_SPI_CLOCK_6") (pintype "bidirectional"))
    )
    (net (code "58") (name "unconnected-(BT1-7_PCM_CLK-Pad7)") (class "Default")
      (node (ref "BT1") (pin "7") (pinfunction "7_PCM_CLK_7") (pintype "bidirectional"))
    )
    (net (code "59") (name "unconnected-(BT1-8_PCM_CLK-Pad8)") (class "Default")
      (node (ref "BT1") (pin "8") (pinfunction "8_PCM_CLK_8") (pintype "bidirectional"))
    )
    (net (code "60") (name "unconnected-(BT1-9_PCM_IN-Pad9)") (class "Default")
      (node (ref "BT1") (pin "9") (pinfunction "9_PCM_IN_9") (pintype "bidirectional"))
    )
    (net (code "61") (name "unconnected-(BT1-10_PCM_OUT-Pad10)") (class "Default")
      (node (ref "BT1") (pin "10") (pinfunction "10_PCM_OUT_10") (pintype "bidirectional"))
    )
    (net (code "62") (name "unconnected-(BT1-23_SPI_CSB-Pad23)") (class "Default")
      (node (ref "BT1") (pin "23") (pinfunction "23_SPI_CSB_23") (pintype "bidirectional"))
    )
    (net (code "63") (name "unconnected-(BT1-24_SPI_MISO-Pad24)") (class "Default")
      (node (ref "BT1") (pin "24") (pinfunction "24_SPI_MISO_24") (pintype "bidirectional"))
    )
    (net (code "64") (name "unconnected-(BT1-Pad30)") (class "Default")
      (node (ref "BT1") (pin "30") (pinfunction "30_30") (pintype "bidirectional"))
    )
    (net (code "65") (name "unconnected-(BT1-Pad35)") (class "Default")
      (node (ref "BT1") (pin "35") (pinfunction "35_35") (pintype "bidirectional"))
    )
    (net (code "66") (name "unconnected-(IC1A-PA6-Pad22)") (class "Default")
      (node (ref "IC1") (pin "22") (pinfunction "PA6_22") (pintype "bidirectional"))
    )
    (net (code "67") (name "unconnected-(IC1A-PA7-Pad23)") (class "Default")
      (node (ref "IC1") (pin "23") (pinfunction "PA7_23") (pintype "bidirectional"))
    )
    (net (code "68") (name "unconnected-(IC1A-PA11-Pad44)") (class "Default")
      (node (ref "IC1") (pin "44") (pinfunction "PA11_44") (pintype "bidirectional"))
    )
    (net (code "69") (name "unconnected-(IC1A-PA12-Pad45)") (class "Default")
      (node (ref "IC1") (pin "45") (pinfunction "PA12_45") (pintype "bidirectional"))
    )
    (net (code "70") (name "unconnected-(IC1A-PA15-Pad50)") (class "Default")
      (node (ref "IC1") (pin "50") (pinfunction "PA15_50") (pintype "bidirectional"))
    )
    (net (code "71") (name "unconnected-(IC1A-PB4-Pad56)") (class "Default")
      (node (ref "IC1") (pin "56") (pinfunction "PB4_56") (pintype "bidirectional"))
    )
    (net (code "72") (name "unconnected-(IC1A-PB5-Pad57)") (class "Default")
      (node (ref "IC1") (pin "57") (pinfunction "PB5_57") (pintype "bidirectional"))
    )
    (net (code "73") (name "unconnected-(IC1A-PB6-Pad58)") (class "Default")
      (node (ref "IC1") (pin "58") (pinfunction "PB6_58") (pintype "bidirectional"))
    )
    (net (code "74") (name "unconnected-(IC1A-PB7-Pad59)") (class "Default")
      (node (ref "IC1") (pin "59") (pinfunction "PB7_59") (pintype "bidirectional"))
    )
    (net (code "75") (name "unconnected-(IC1A-PB8-Pad61)") (class "Default")
      (node (ref "IC1") (pin "61") (pinfunction "PB8_61") (pintype "bidirectional"))
    )
    (net (code "76") (name "unconnected-(IC1A-PB9-Pad62)") (class "Default")
      (node (ref "IC1") (pin "62") (pinfunction "PB9_62") (pintype "bidirectional"))
    )
    (net (code "77") (name "unconnected-(IC1A-PB12-Pad33)") (class "Default")
      (node (ref "IC1") (pin "33") (pinfunction "PB12_33") (pintype "bidirectional"))
    )
    (net (code "78") (name "unconnected-(IC1A-PB13-Pad34)") (class "Default")
      (node (ref "IC1") (pin "34") (pinfunction "PB13_34") (pintype "bidirectional"))
    )
    (net (code "79") (name "unconnected-(IC1A-PB14-Pad35)") (class "Default")
      (node (ref "IC1") (pin "35") (pinfunction "PB14_35") (pintype "bidirectional"))
    )
    (net (code "80") (name "unconnected-(IC1A-PB15-Pad36)") (class "Default")
      (node (ref "IC1") (pin "36") (pinfunction "PB15_36") (pintype "bidirectional"))
    )
    (net (code "81") (name "unconnected-(IC1A-PC2-Pad10)") (class "Default")
      (node (ref "IC1") (pin "10") (pinfunction "PC2_10") (pintype "bidirectional"))
    )
    (net (code "82") (name "unconnected-(IC1A-PC3-Pad11)") (class "Default")
      (node (ref "IC1") (pin "11") (pinfunction "PC3_11") (pintype "bidirectional"))
    )
    (net (code "83") (name "unconnected-(IC1A-PC4-Pad24)") (class "Default")
      (node (ref "IC1") (pin "24") (pinfunction "PC4_24") (pintype "bidirectional"))
    )
    (net (code "84") (name "unconnected-(IC1A-PC5-Pad25)") (class "Default")
      (node (ref "IC1") (pin "25") (pinfunction "PC5_25") (pintype "bidirectional"))
    )
    (net (code "85") (name "unconnected-(IC1A-PC6-Pad37)") (class "Default")
      (node (ref "IC1") (pin "37") (pinfunction "PC6_37") (pintype "bidirectional"))
    )
    (net (code "86") (name "unconnected-(IC1A-PC7-Pad38)") (class "Default")
      (node (ref "IC1") (pin "38") (pinfunction "PC7_38") (pintype "bidirectional"))
    )
    (net (code "87") (name "unconnected-(IC1A-PC8-Pad39)") (class "Default")
      (node (ref "IC1") (pin "39") (pinfunction "PC8_39") (pintype "bidirectional"))
    )
    (net (code "88") (name "unconnected-(IC1A-PC10-Pad51)") (class "Default")
      (node (ref "IC1") (pin "51") (pinfunction "PC10_51") (pintype "bidirectional"))
    )
    (net (code "89") (name "unconnected-(IC1A-PC11-Pad52)") (class "Default")
      (node (ref "IC1") (pin "52") (pinfunction "PC11_52") (pintype "bidirectional"))
    )
    (net (code "90") (name "unconnected-(IC1A-PC12-Pad53)") (class "Default")
      (node (ref "IC1") (pin "53") (pinfunction "PC12_53") (pintype "bidirectional"))
    )
    (net (code "91") (name "unconnected-(IC1A-PC13-Pad2)") (class "Default")
      (node (ref "IC1") (pin "2") (pinfunction "PC13_2") (pintype "bidirectional"))
    )
    (net (code "92") (name "unconnected-(IC1A-PC14-Pad3)") (class "Default")
      (node (ref "IC1") (pin "3") (pinfunction "PC14_3") (pintype "bidirectional"))
    )
    (net (code "93") (name "unconnected-(IC1A-PC15-Pad4)") (class "Default")
      (node (ref "IC1") (pin "4") (pinfunction "PC15_4") (pintype "bidirectional"))
    )
    (net (code "94") (name "unconnected-(IC1A-PD2-Pad54)") (class "Default")
      (node (ref "IC1") (pin "54") (pinfunction "PD2_54") (pintype "bidirectional"))
    )
    (net (code "95") (name "unconnected-(IC4-PadNC1)") (class "Default")
      (node (ref "IC4") (pin "NC1") (pinfunction "NC1_NC1") (pintype "bidirectional"))
    )
    (net (code "96") (name "unconnected-(IC4-PadNC2)") (class "Default")
      (node (ref "IC4") (pin "NC2") (pinfunction "NC2_NC2") (pintype "bidirectional"))
    )
    (net (code "97") (name "unconnected-(IC4-PadNC3)") (class "Default")
      (node (ref "IC4") (pin "NC3") (pinfunction "NC3_NC3") (pintype "bidirectional"))
    )
    (net (code "98") (name "unconnected-(IC4-PadNC4)") (class "Default")
      (node (ref "IC4") (pin "NC4") (pinfunction "NC4_NC4") (pintype "bidirectional"))
    )
    (net (code "99") (name "unconnected-(IC4-PadNC5)") (class "Default")
      (node (ref "IC4") (pin "NC5") (pinfunction "NC5_NC5") (pintype "bidirectional"))
    )
    (net (code "100") (name "unconnected-(LM2674-5V-BUCK1-2-*-Pad2)") (class "Default")
      (node (ref "LM2674-5V-BUCK1") (pin "2") (pinfunction "2-*_2") (pintype "bidirectional"))
    )
    (net (code "101") (name "unconnected-(LM2674-5V-BUCK1-3-*-Pad3)") (class "Default")
      (node (ref "LM2674-5V-BUCK1") (pin "3") (pinfunction "3-*_3") (pintype "bidirectional"))
    )
    (net (code "102") (name "unconnected-(LM2674-5V-BUCK1-5-ON{slash}OFF-Pad5)") (class "Default")
      (node (ref "LM2674-5V-BUCK1") (pin "5") (pinfunction "5-ON/OFF_5") (pintype "bidirectional"))
    )
  )
)
